# STM32.net
KiCad netlist of a schematic drawn in Altium Designer
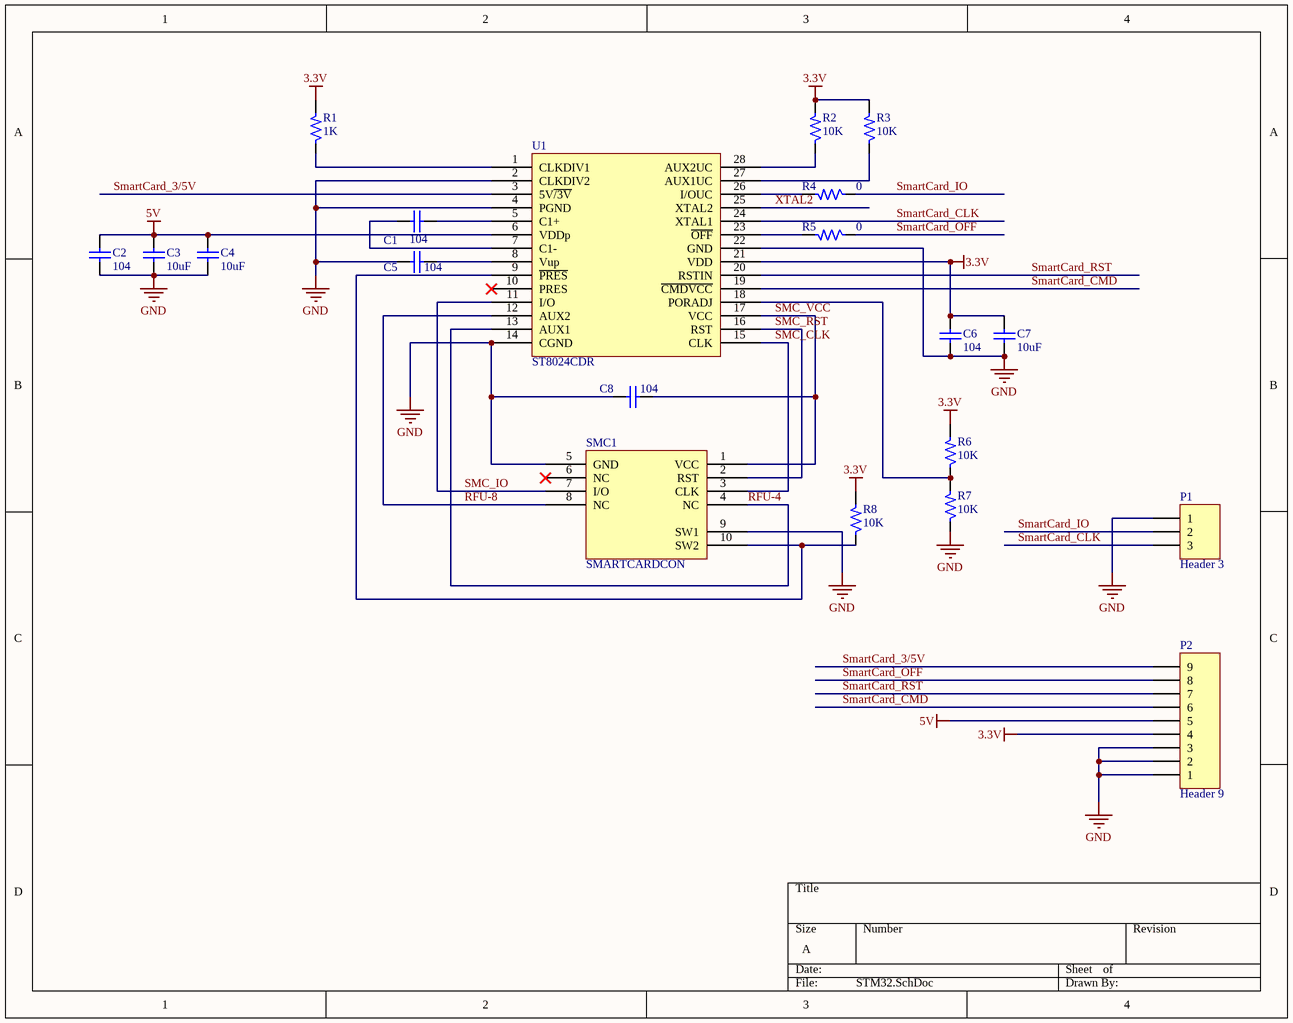
[diagram p0: STM32.SchDoc]

(export (version "E")
  (design (tool "Eeschema 10.0.6"))
  (components
    (comp (ref "C1")
      (value "104")
      (footprint "TU_SMD_0805")
      (description "Ceramic Chip Capacitor - Standard")
      (fields (field (name "PUBLISHER") "Altium Limited"))
      (libsource (lib "mySch") (part "Capacitor 0805"))
    )
    (comp (ref "C2")
      (value "104")
      (footprint "TU_SMD_0805")
      (description "Ceramic Chip Capacitor - Standard")
      (fields (field (name "PUBLISHER") "Altium Limited"))
      (libsource (lib "mySch") (part "Capacitor 0805"))
    )
    (comp (ref "C3")
      (value "10uF")
      (footprint "TU_SMD_0805")
      (description "Ceramic Chip Capacitor - Standard")
      (fields (field (name "PUBLISHER") "Altium Limited"))
      (libsource (lib "mySch") (part "Capacitor 0805"))
    )
    (comp (ref "C4")
      (value "10uF")
      (footprint "TU_SMD_0805")
      (description "Ceramic Chip Capacitor - Standard")
      (fields (field (name "PUBLISHER") "Altium Limited"))
      (libsource (lib "mySch") (part "Capacitor 0805"))
    )
    (comp (ref "C5")
      (value "104")
      (footprint "TU_SMD_0805")
      (description "Ceramic Chip Capacitor - Standard")
      (fields (field (name "PUBLISHER") "Altium Limited"))
      (libsource (lib "mySch") (part "Capacitor 0805"))
    )
    (comp (ref "C6")
      (value "104")
      (footprint "TU_SMD_0805")
      (description "Ceramic Chip Capacitor - Standard")
      (fields (field (name "PUBLISHER") "Altium Limited"))
      (libsource (lib "mySch") (part "Capacitor 0805"))
    )
    (comp (ref "C7")
      (value "10uF")
      (footprint "TU_SMD_0805")
      (description "Ceramic Chip Capacitor - Standard")
      (fields (field (name "PUBLISHER") "Altium Limited"))
      (libsource (lib "mySch") (part "Capacitor 0805"))
    )
    (comp (ref "C8")
      (value "104")
      (footprint "TU_SMD_0805")
      (description "Ceramic Chip Capacitor - Standard")
      (fields (field (name "PUBLISHER") "Altium Limited"))
      (libsource (lib "mySch") (part "Capacitor 0805"))
    )
    (comp (ref "P1")
      (value "Header 3")
      (footprint "HDR1X3")
      (description "Header, 3-Pin")
      (fields (field (name "PUBLISHER") "Altium Limited"))
      (libsource (lib "Miscellaneous Connectors") (part "Header 3"))
    )
    (comp (ref "P2")
      (value "Header 9")
      (footprint "HDR1X9")
      (description "Header, 9-Pin")
      (fields (field (name "PUBLISHER") "Altium Limited"))
      (libsource (lib "Miscellaneous Connectors") (part "Header 9"))
    )
    (comp (ref "R1")
      (value "1K")
      (footprint "Tro SMD 0805")
      (description "Resistor 1/4W")
      (libsource (lib "mySch") (part "R"))
    )
    (comp (ref "R2")
      (value "10K")
      (footprint "Tro SMD 0805")
      (description "Resistor 1/4W")
      (libsource (lib "mySch") (part "R"))
    )
    (comp (ref "R3")
      (value "10K")
      (footprint "Tro SMD 0805")
      (description "Resistor 1/4W")
      (libsource (lib "mySch") (part "R"))
    )
    (comp (ref "R4")
      (value "0")
      (footprint "Tro SMD 0805")
      (description "Resistor 1/4W")
      (libsource (lib "mySch") (part "R"))
    )
    (comp (ref "R5")
      (value "0")
      (footprint "Tro SMD 0805")
      (description "Resistor 1/4W")
      (libsource (lib "mySch") (part "R"))
    )
    (comp (ref "R6")
      (value "10K")
      (footprint "Tro SMD 0805")
      (description "Resistor 1/4W")
      (libsource (lib "mySch") (part "R"))
    )
    (comp (ref "R7")
      (value "10K")
      (footprint "Tro SMD 0805")
      (description "Resistor 1/4W")
      (libsource (lib "mySch") (part "R"))
    )
    (comp (ref "R8")
      (value "10K")
      (footprint "Tro SMD 0805")
      (description "Resistor 1/4W")
      (libsource (lib "mySch") (part "R"))
    )
    (comp (ref "SMC1")
      (value "SMARTCARDCON")
      (footprint "Smartcart_CON")
      (libsource (lib "Schlib1") (part "SMARTCARDCON"))
    )
    (comp (ref "U1")
      (value "ST8024CDR")
      (footprint "SOIC-SO28_N")
      (libsource (lib "Schlib1") (part "ST8024"))
    )
  )
  (nets
    (net (code "1") (name "/RFU-4") (class "Default")
      (node (ref "SMC1") (pin "4") (pinfunction "NC_4") (pintype "passive"))
      (node (ref "U1") (pin "13") (pinfunction "AUX1_13") (pintype "passive"))
    )
    (net (code "2") (name "/RFU-8") (class "Default")
      (node (ref "SMC1") (pin "8") (pinfunction "NC_8") (pintype "passive"))
      (node (ref "U1") (pin "12") (pinfunction "AUX2_12") (pintype "passive"))
    )
    (net (code "3") (name "/SMC_CLK") (class "Default")
      (node (ref "SMC1") (pin "3") (pinfunction "CLK_3") (pintype "passive"))
      (node (ref "U1") (pin "15") (pinfunction "CLK_15") (pintype "passive"))
    )
    (net (code "4") (name "/SMC_IO") (class "Default")
      (node (ref "SMC1") (pin "7") (pinfunction "I/O_7") (pintype "passive"))
      (node (ref "U1") (pin "11") (pinfunction "I/O_11") (pintype "passive"))
    )
    (net (code "5") (name "/SMC_RST") (class "Default")
      (node (ref "SMC1") (pin "2") (pinfunction "RST_2") (pintype "passive"))
      (node (ref "U1") (pin "16") (pinfunction "RST_16") (pintype "passive"))
    )
    (net (code "6") (name "/SMC_VCC") (class "Default")
      (node (ref "C8") (pin "1") (pinfunction "1_1") (pintype "passive"))
      (node (ref "SMC1") (pin "1") (pinfunction "VCC_1") (pintype "passive"))
      (node (ref "U1") (pin "17") (pinfunction "VCC_17") (pintype "passive"))
    )
    (net (code "7") (name "/SmartCard_3{slash}5V") (class "Default")
      (node (ref "P2") (pin "9") (pinfunction "9_9") (pintype "passive"))
      (node (ref "U1") (pin "3") (pinfunction "5V~{/3V}_3") (pintype "passive"))
    )
    (net (code "8") (name "/SmartCard_CLK") (class "Default")
      (node (ref "P1") (pin "3") (pinfunction "3_3") (pintype "passive"))
      (node (ref "U1") (pin "24") (pinfunction "XTAL1_24") (pintype "passive"))
    )
    (net (code "9") (name "/SmartCard_CMD") (class "Default")
      (node (ref "P2") (pin "6") (pinfunction "6_6") (pintype "passive"))
      (node (ref "U1") (pin "19") (pinfunction "~{CMDVCC}_19") (pintype "passive"))
    )
    (net (code "10") (name "/SmartCard_IO") (class "Default")
      (node (ref "P1") (pin "2") (pinfunction "2_2") (pintype "passive"))
      (node (ref "R4") (pin "1") (pinfunction "1_1") (pintype "passive"))
    )
    (net (code "11") (name "/SmartCard_OFF") (class "Default")
      (node (ref "P2") (pin "8") (pinfunction "8_8") (pintype "passive"))
      (node (ref "R5") (pin "1") (pinfunction "1_1") (pintype "passive"))
    )
    (net (code "12") (name "/SmartCard_RST") (class "Default")
      (node (ref "P2") (pin "7") (pinfunction "7_7") (pintype "passive"))
      (node (ref "U1") (pin "20") (pinfunction "RSTIN_20") (pintype "passive"))
    )
    (net (code "13") (name "/XTAL2") (class "Default")
      (node (ref "U1") (pin "25") (pinfunction "XTAL2_25") (pintype "passive"))
    )
    (net (code "14") (name "3.3V") (class "Default")
      (node (ref "C6") (pin "1") (pinfunction "1_1") (pintype "passive"))
      (node (ref "C7") (pin "1") (pinfunction "1_1") (pintype "passive"))
      (node (ref "P2") (pin "4") (pinfunction "4_4") (pintype "passive"))
      (node (ref "R1") (pin "2") (pinfunction "2_2") (pintype "passive"))
      (node (ref "R2") (pin "2") (pinfunction "2_2") (pintype "passive"))
      (node (ref "R3") (pin "2") (pinfunction "2_2") (pintype "passive"))
      (node (ref "R6") (pin "2") (pinfunction "2_2") (pintype "passive"))
      (node (ref "R8") (pin "2") (pinfunction "2_2") (pintype "passive"))
      (node (ref "U1") (pin "21") (pinfunction "VDD_21") (pintype "passive"))
    )
    (net (code "15") (name "5V") (class "Default")
      (node (ref "C2") (pin "1") (pinfunction "1_1") (pintype "passive"))
      (node (ref "C3") (pin "1") (pinfunction "1_1") (pintype "passive"))
      (node (ref "C4") (pin "1") (pinfunction "1_1") (pintype "passive"))
      (node (ref "P2") (pin "5") (pinfunction "5_5") (pintype "passive"))
      (node (ref "U1") (pin "6") (pinfunction "VDDp_6") (pintype "passive"))
    )
    (net (code "16") (name "GND") (class "Default")
      (node (ref "C2") (pin "2") (pinfunction "2_2") (pintype "passive"))
      (node (ref "C3") (pin "2") (pinfunction "2_2") (pintype "passive"))
      (node (ref "C4") (pin "2") (pinfunction "2_2") (pintype "passive"))
      (node (ref "C5") (pin "2") (pinfunction "2_2") (pintype "passive"))
      (node (ref "C6") (pin "2") (pinfunction "2_2") (pintype "passive"))
      (node (ref "C7") (pin "2") (pinfunction "2_2") (pintype "passive"))
      (node (ref "C8") (pin "2") (pinfunction "2_2") (pintype "passive"))
      (node (ref "P1") (pin "1") (pinfunction "1_1") (pintype "passive"))
      (node (ref "P2") (pin "1") (pinfunction "1_1") (pintype "passive"))
      (node (ref "P2") (pin "2") (pinfunction "2_2") (pintype "passive"))
      (node (ref "P2") (pin "3") (pinfunction "3_3") (pintype "passive"))
      (node (ref "R7") (pin "1") (pinfunction "1_1") (pintype "passive"))
      (node (ref "SMC1") (pin "5") (pinfunction "GND_5") (pintype "passive"))
      (node (ref "SMC1") (pin "9") (pinfunction "SW1_9") (pintype "passive"))
      (node (ref "U1") (pin "14") (pinfunction "CGND_14") (pintype "passive"))
      (node (ref "U1") (pin "2") (pinfunction "CLKDIV2_2") (pintype "passive"))
      (node (ref "U1") (pin "22") (pinfunction "GND_22") (pintype "passive"))
      (node (ref "U1") (pin "4") (pinfunction "PGND_4") (pintype "passive"))
    )
    (net (code "17") (name "Net-(SMC1-SW2)") (class "Default")
      (node (ref "R8") (pin "1") (pinfunction "1_1") (pintype "passive"))
      (node (ref "SMC1") (pin "10") (pinfunction "SW2_10") (pintype "passive"))
      (node (ref "U1") (pin "9") (pinfunction "~{PRES}_9") (pintype "passive"))
    )
    (net (code "18") (name "Net-(U1-AUX1UC)") (class "Default")
      (node (ref "R3") (pin "1") (pinfunction "1_1") (pintype "passive"))
      (node (ref "U1") (pin "27") (pinfunction "AUX1UC_27") (pintype "passive"))
    )
    (net (code "19") (name "Net-(U1-AUX2UC)") (class "Default")
      (node (ref "R2") (pin "1") (pinfunction "1_1") (pintype "passive"))
      (node (ref "U1") (pin "28") (pinfunction "AUX2UC_28") (pintype "passive"))
    )
    (net (code "20") (name "Net-(U1-C1+)") (class "Default")
      (node (ref "C1") (pin "1") (pinfunction "1_1") (pintype "passive"))
      (node (ref "U1") (pin "5") (pinfunction "C1+_5") (pintype "passive"))
    )
    (net (code "21") (name "Net-(U1-C1-)") (class "Default")
      (node (ref "C1") (pin "2") (pinfunction "2_2") (pintype "passive"))
      (node (ref "U1") (pin "7") (pinfunction "C1-_7") (pintype "passive"))
    )
    (net (code "22") (name "Net-(U1-CLKDIV1)") (class "Default")
      (node (ref "R1") (pin "1") (pinfunction "1_1") (pintype "passive"))
      (node (ref "U1") (pin "1") (pinfunction "CLKDIV1_1") (pintype "passive"))
    )
    (net (code "23") (name "Net-(U1-I{slash}OUC)") (class "Default")
      (node (ref "R4") (pin "2") (pinfunction "2_2") (pintype "passive"))
      (node (ref "U1") (pin "26") (pinfunction "I/OUC_26") (pintype "passive"))
    )
    (net (code "24") (name "Net-(U1-PORADJ)") (class "Default")
      (node (ref "R6") (pin "1") (pinfunction "1_1") (pintype "passive"))
      (node (ref "R7") (pin "2") (pinfunction "2_2") (pintype "passive"))
      (node (ref "U1") (pin "18") (pinfunction "PORADJ_18") (pintype "passive"))
    )
    (net (code "25") (name "Net-(U1-Vup)") (class "Default")
      (node (ref "C5") (pin "1") (pinfunction "1_1") (pintype "passive"))
      (node (ref "U1") (pin "8") (pinfunction "Vup_8") (pintype "passive"))
    )
    (net (code "26") (name "Net-(U1-~{OFF})") (class "Default")
      (node (ref "R5") (pin "2") (pinfunction "2_2") (pintype "passive"))
      (node (ref "U1") (pin "23") (pinfunction "~{OFF}_23") (pintype "passive"))
    )
    (net (code "27") (name "unconnected-(SMC1-NC-Pad6)") (class "Default")
      (node (ref "SMC1") (pin "6") (pinfunction "NC_6") (pintype "passive+no_connect"))
    )
    (net (code "28") (name "unconnected-(U1-PRES-Pad10)") (class "Default")
      (node (ref "U1") (pin "10") (pinfunction "PRES_10") (pintype "passive+no_connect"))
    )
  )
)
